# power_node.net
KiCad netlist of a schematic drawn in Altium Designer
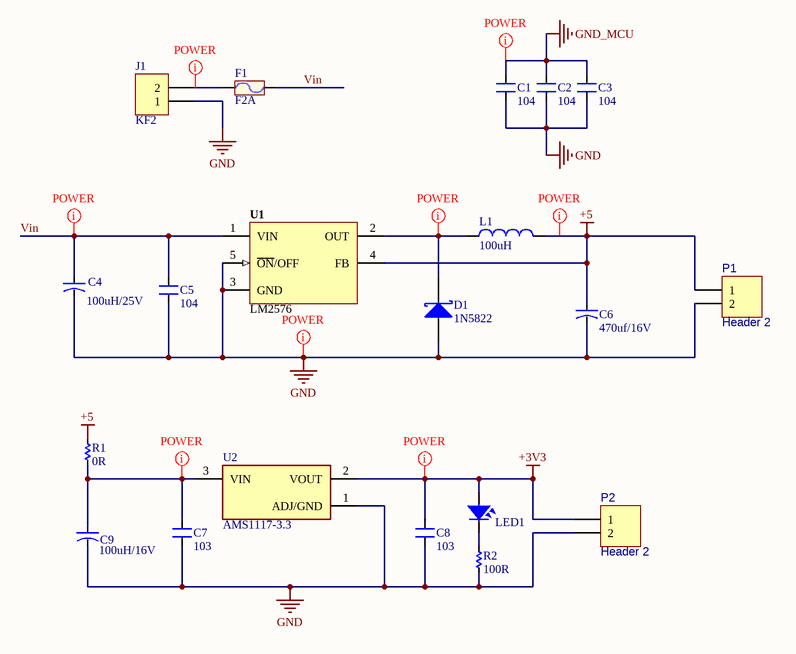
[diagram p0: power_node.SchDoc]

(export (version "E")
  (design (tool "Eeschema 10.0.6"))
  (components
    (comp (ref "C1")
      (value "104")
      (footprint "SM-0805")
      (description "Cap SMD")
      (libsource (lib "syhaunguyen") (part "CM"))
    )
    (comp (ref "C2")
      (value "104")
      (footprint "SM-0805")
      (description "Cap SMD")
      (libsource (lib "syhaunguyen") (part "CM"))
    )
    (comp (ref "C3")
      (value "104")
      (footprint "SM-0805")
      (description "Cap SMD")
      (libsource (lib "syhaunguyen") (part "CM"))
    )
    (comp (ref "C4")
      (value "100uH/25V")
      (footprint "CAP-ALU-SMD-6.3x7.7x2.2")
      (description "Polarized Capacitor (Axial)")
      (fields (field (name "PUBLISHER") "Altium Limited"))
      (libsource (lib "TechMT.VN_Lib_Project v2") (part "CN-ALU-SMD"))
    )
    (comp (ref "C5")
      (value "104")
      (footprint "SM-0805")
      (description "Cap SMD")
      (libsource (lib "syhaunguyen") (part "CM"))
    )
    (comp (ref "C6")
      (value "470uf/16V")
      (footprint "CAP-ALU-SMD-6.3x7.7x2.2")
      (description "Polarized Capacitor (Axial)")
      (fields (field (name "PUBLISHER") "Altium Limited"))
      (libsource (lib "TechMT.VN_Lib_Project v2") (part "CN-ALU-SMD"))
    )
    (comp (ref "C7")
      (value "103")
      (footprint "SM-0805")
      (description "Cap SMD")
      (libsource (lib "syhaunguyen") (part "CM"))
    )
    (comp (ref "C8")
      (value "103")
      (footprint "SM-0805")
      (description "Cap SMD")
      (libsource (lib "syhaunguyen") (part "CM"))
    )
    (comp (ref "C9")
      (value "100uH/16V")
      (footprint "CAP-ALU-SMD-6.3x7.7x2.2")
      (description "Polarized Capacitor (Axial)")
      (fields (field (name "PUBLISHER") "Altium Limited"))
      (libsource (lib "TechMT.VN_Lib_Project v2") (part "CN-ALU-SMD"))
    )
    (comp (ref "D1")
      (value "1N5822")
      (footprint "Diode_SS34")
      (description "Schottky diode")
      (libsource (lib "AYRIC Library") (part "1N5819"))
    )
    (comp (ref "F1")
      (value "F2A")
      (footprint "FUSE2")
      (description "Fuse")
      (fields (field (name "DESIGNED BY") "VanDungEvn"))
      (libsource (lib "TechMT.VN_Lib_Project v2") (part "Fuse"))
    )
    (comp (ref "J1")
      (value "KF2")
      (footprint "KF2-5.08")
      (fields
        (field (name "MANUFACTURER") "Würth Elektronik eiSos GmbH")
        (field (name "PARTNO") "691103110002")
        (field (name "CREATED BY") "Karrer Zheng")
      )
      (libsource (lib "TechMT.VN_Lib_Project v2") (part "KF2"))
    )
    (comp (ref "L1")
      (value "100uH")
      (footprint "inductor_smd")
      (fields (field (name "Comment") "Inductor") (field (name "PUBLISHER") "Altium Limited"))
      (libsource (lib "AYRIC Library") (part "Inductor"))
    )
    (comp (ref "LED1")
      (value "LED")
      (footprint "LED-0805-Green")
      (libsource (lib "TechMT.VN_Lib_Project v2") (part "LED SMD"))
    )
    (comp (ref "P1")
      (value "Header 2")
      (footprint "HDR1X2")
      (description "Header, 2-Pin")
      (fields (field (name "PUBLISHER") "Altium Limited"))
      (libsource (lib "NBBLib 14-03-2012") (part "Header 2"))
    )
    (comp (ref "P2")
      (value "Header 2")
      (footprint "HDR1X2")
      (description "Header, 2-Pin")
      (fields (field (name "PUBLISHER") "Altium Limited"))
      (libsource (lib "NBBLib 14-03-2012") (part "Header 2"))
    )
    (comp (ref "R1")
      (value "0R")
      (footprint "RES-SMD-0805")
      (description "Resistor")
      (fields
        (field (name "MANUFACTURER") "Generic Components")
        (field (name "PUBLISHER") "Altium Hobart Technology Centre")
      )
      (libsource (lib "TechMT.VN_Lib_Project v2") (part "Res-SMD"))
    )
    (comp (ref "R2")
      (value "100R")
      (footprint "RES-SMD-0805")
      (description "Resistor")
      (fields
        (field (name "MANUFACTURER") "Generic Components")
        (field (name "PUBLISHER") "Altium Hobart Technology Centre")
      )
      (libsource (lib "TechMT.VN_Lib_Project v2") (part "Res-SMD"))
    )
    (comp (ref "U1")
      (value "LM2576")
      (footprint "TO263")
      (libsource (lib "TechMT.VN_Lib_Project v2") (part "LM2576"))
    )
    (comp (ref "U2")
      (value "AMS1117-3.3")
      (footprint "SOT229P700X180-4N")
      (description "Sot223/Pkg 1-Amp 3.3-Volt Low Drop Out Voltage Regulatator")
      (fields (field (name "MF") "Advanced Monolithic Systems"))
      (libsource (lib "AMS1117-3.3") (part "AMS1117-3.3"))
    )
  )
  (nets
    (net (code "1") (name "+3V3") (class "Default")
      (node (ref "C8") (pin "1") (pinfunction "1_1") (pintype "passive"))
      (node (ref "LED1") (pin "1") (pinfunction "1_1") (pintype "passive"))
      (node (ref "P2") (pin "1") (pinfunction "1_1") (pintype "passive"))
      (node (ref "U2") (pin "2") (pinfunction "VOUT_2") (pintype "passive"))
    )
    (net (code "2") (name "+5") (class "Default")
      (node (ref "C6") (pin "1") (pinfunction "1_1") (pintype "passive"))
      (node (ref "L1") (pin "2") (pinfunction "2_2") (pintype "passive"))
      (node (ref "P1") (pin "1") (pinfunction "1_1") (pintype "passive"))
      (node (ref "R1") (pin "1") (pinfunction "1_1") (pintype "passive"))
      (node (ref "U1") (pin "4") (pinfunction "FB_4") (pintype "passive"))
    )
    (net (code "3") (name "/Vin") (class "Default")
      (node (ref "C4") (pin "1") (pinfunction "1_1") (pintype "passive"))
      (node (ref "C5") (pin "1") (pinfunction "1_1") (pintype "passive"))
      (node (ref "F1") (pin "2") (pinfunction "2_2") (pintype "passive"))
      (node (ref "U1") (pin "1") (pinfunction "VIN_1") (pintype "power_in"))
    )
    (net (code "4") (name "GND") (class "Default")
      (node (ref "C1") (pin "1") (pinfunction "1_1") (pintype "passive"))
      (node (ref "C2") (pin "1") (pinfunction "1_1") (pintype "passive"))
      (node (ref "C3") (pin "1") (pinfunction "1_1") (pintype "passive"))
      (node (ref "C4") (pin "2") (pinfunction "2_2") (pintype "passive"))
      (node (ref "C5") (pin "2") (pinfunction "2_2") (pintype "passive"))
      (node (ref "C6") (pin "2") (pinfunction "2_2") (pintype "passive"))
      (node (ref "C7") (pin "2") (pinfunction "2_2") (pintype "passive"))
      (node (ref "C8") (pin "2") (pinfunction "2_2") (pintype "passive"))
      (node (ref "C9") (pin "2") (pinfunction "2_2") (pintype "passive"))
      (node (ref "D1") (pin "1") (pinfunction "A_1") (pintype "passive"))
      (node (ref "J1") (pin "1") (pinfunction "1_1") (pintype "passive"))
      (node (ref "P1") (pin "2") (pinfunction "2_2") (pintype "passive"))
      (node (ref "P2") (pin "2") (pinfunction "2_2") (pintype "passive"))
      (node (ref "R2") (pin "2") (pinfunction "2_2") (pintype "passive"))
      (node (ref "U1") (pin "3") (pinfunction "GND_3") (pintype "power_in"))
      (node (ref "U1") (pin "5") (pinfunction "~{ON}/OFF_5") (pintype "input"))
      (node (ref "U2") (pin "1") (pinfunction "ADJ/GND_1") (pintype "power_in"))
    )
    (net (code "5") (name "GND_MCU") (class "Default")
      (node (ref "C1") (pin "2") (pinfunction "2_2") (pintype "passive"))
      (node (ref "C2") (pin "2") (pinfunction "2_2") (pintype "passive"))
      (node (ref "C3") (pin "2") (pinfunction "2_2") (pintype "passive"))
    )
    (net (code "6") (name "Net-(D1-K)") (class "Default")
      (node (ref "D1") (pin "2") (pinfunction "K_2") (pintype "passive"))
      (node (ref "L1") (pin "1") (pinfunction "1_1") (pintype "passive"))
      (node (ref "U1") (pin "2") (pinfunction "OUT_2") (pintype "power_in"))
    )
    (net (code "7") (name "Net-(F1-Pad1)") (class "Default")
      (node (ref "F1") (pin "1") (pinfunction "1_1") (pintype "passive"))
      (node (ref "J1") (pin "2") (pinfunction "2_2") (pintype "passive"))
    )
    (net (code "8") (name "Net-(LED1-Pad2)") (class "Default")
      (node (ref "LED1") (pin "2") (pinfunction "2_2") (pintype "passive"))
      (node (ref "R2") (pin "1") (pinfunction "1_1") (pintype "passive"))
    )
    (net (code "9") (name "Net-(U2-VIN)") (class "Default")
      (node (ref "C7") (pin "1") (pinfunction "1_1") (pintype "passive"))
      (node (ref "C9") (pin "1") (pinfunction "1_1") (pintype "passive"))
      (node (ref "R1") (pin "2") (pinfunction "2_2") (pintype "passive"))
      (node (ref "U2") (pin "3") (pinfunction "VIN_3") (pintype "passive"))
    )
  )
)
